# MCU.net
KiCad netlist of a schematic drawn in Altium Designer
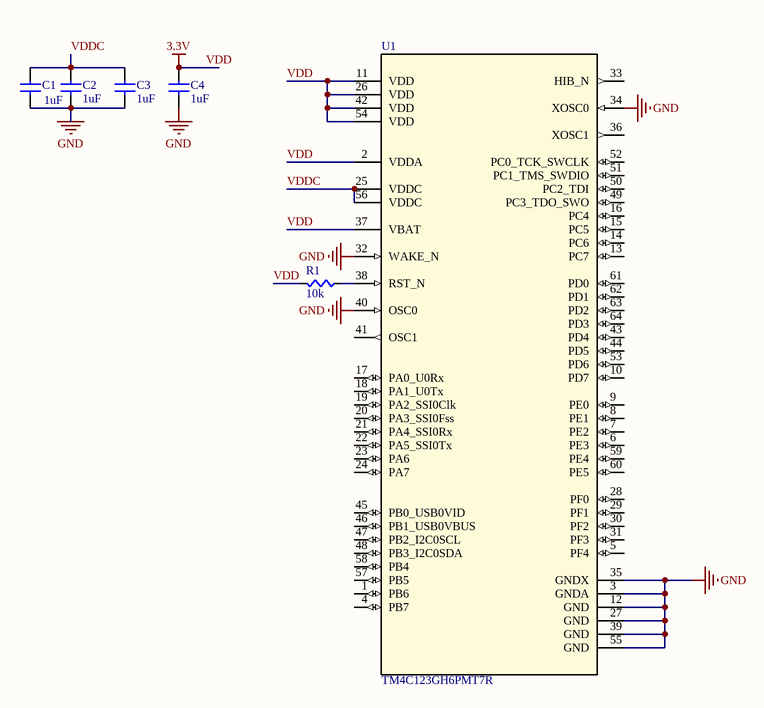
[diagram p0: MCU.SchDoc]

(export (version "E")
  (design (tool "Eeschema 10.0.6"))
  (components
    (comp (ref "C1")
      (value "1uF")
      (footprint "CAPC0805")
      (fields (field (name "Comment") "Cap"))
      (libsource (lib "Passives") (part "Cap"))
    )
    (comp (ref "C2")
      (value "1uF")
      (footprint "CAPC0805")
      (fields (field (name "Comment") "Cap"))
      (libsource (lib "Passives") (part "Cap"))
    )
    (comp (ref "C3")
      (value "1uF")
      (footprint "CAPC0805")
      (fields (field (name "Comment") "Cap"))
      (libsource (lib "Passives") (part "Cap"))
    )
    (comp (ref "C4")
      (value "1uF")
      (footprint "CAPC0805")
      (fields (field (name "Comment") "Cap"))
      (libsource (lib "Passives") (part "Cap"))
    )
    (comp (ref "R1")
      (value "10k")
      (footprint "RES0603")
      (fields (field (name "Comment") "Res"))
      (libsource (lib "Passives") (part "Res"))
    )
    (comp (ref "U1")
      (value "TM4C123GH6PMT7R")
      (footprint "TM4C123GH6PMT7R_L")
      (description "Imported")
      (fields
        (field (name "PARTNUMBER") "TM4C123GH6PMTR")
        (field (name "ALTERNATE_PARTNUMBER") "TM4C123GH6PMT")
      )
      (libsource (lib "ICs") (part "TM4C123GH6PMT7R"))
    )
  )
  (nets
    (net (code "1") (name "/VDDC") (class "Default")
      (node (ref "C1") (pin "1") (pinfunction "A_1") (pintype "passive"))
      (node (ref "C2") (pin "1") (pinfunction "A_1") (pintype "passive"))
      (node (ref "C3") (pin "1") (pinfunction "A_1") (pintype "passive"))
      (node (ref "U1") (pin "25") (pinfunction "VDDC_25") (pintype "power_in"))
      (node (ref "U1") (pin "56") (pinfunction "VDDC_56") (pintype "power_in"))
    )
    (net (code "2") (name "3.3V") (class "Default")
      (node (ref "C4") (pin "1") (pinfunction "A_1") (pintype "passive"))
      (node (ref "R1") (pin "1") (pinfunction "A_1") (pintype "passive"))
      (node (ref "U1") (pin "11") (pinfunction "VDD_11") (pintype "power_in"))
      (node (ref "U1") (pin "2") (pinfunction "VDDA_2") (pintype "power_in"))
      (node (ref "U1") (pin "26") (pinfunction "VDD_26") (pintype "power_in"))
      (node (ref "U1") (pin "37") (pinfunction "VBAT_37") (pintype "power_in"))
      (node (ref "U1") (pin "42") (pinfunction "VDD_42") (pintype "power_in"))
      (node (ref "U1") (pin "54") (pinfunction "VDD_54") (pintype "power_in"))
    )
    (net (code "3") (name "GND") (class "Default")
      (node (ref "C1") (pin "2") (pinfunction "B_2") (pintype "passive"))
      (node (ref "C2") (pin "2") (pinfunction "B_2") (pintype "passive"))
      (node (ref "C3") (pin "2") (pinfunction "B_2") (pintype "passive"))
      (node (ref "C4") (pin "2") (pinfunction "B_2") (pintype "passive"))
      (node (ref "U1") (pin "12") (pinfunction "GND_12") (pintype "power_in"))
      (node (ref "U1") (pin "27") (pinfunction "GND_27") (pintype "power_in"))
      (node (ref "U1") (pin "3") (pinfunction "GNDA_3") (pintype "power_in"))
      (node (ref "U1") (pin "32") (pinfunction "WAKE_N_32") (pintype "input"))
      (node (ref "U1") (pin "34") (pinfunction "XOSC0_34") (pintype "input"))
      (node (ref "U1") (pin "35") (pinfunction "GNDX_35") (pintype "power_in"))
      (node (ref "U1") (pin "39") (pinfunction "GND_39") (pintype "power_in"))
      (node (ref "U1") (pin "40") (pinfunction "OSC0_40") (pintype "input"))
      (node (ref "U1") (pin "55") (pinfunction "GND_55") (pintype "power_in"))
    )
    (net (code "4") (name "Net-(R1-B)") (class "Default")
      (node (ref "R1") (pin "2") (pinfunction "B_2") (pintype "passive"))
      (node (ref "U1") (pin "38") (pinfunction "RST_N_38") (pintype "input"))
    )
    (net (code "5") (name "unconnected-(U1-HIB_N-Pad33)") (class "Default")
      (node (ref "U1") (pin "33") (pinfunction "HIB_N_33") (pintype "output"))
    )
    (net (code "6") (name "unconnected-(U1-OSC1-Pad41)") (class "Default")
      (node (ref "U1") (pin "41") (pinfunction "OSC1_41") (pintype "output"))
    )
    (net (code "7") (name "unconnected-(U1-PA0_U0Rx-Pad17)") (class "Default")
      (node (ref "U1") (pin "17") (pinfunction "PA0_U0Rx_17") (pintype "bidirectional"))
    )
    (net (code "8") (name "unconnected-(U1-PA1_U0Tx-Pad18)") (class "Default")
      (node (ref "U1") (pin "18") (pinfunction "PA1_U0Tx_18") (pintype "bidirectional"))
    )
    (net (code "9") (name "unconnected-(U1-PA2_SSI0Clk-Pad19)") (class "Default")
      (node (ref "U1") (pin "19") (pinfunction "PA2_SSI0Clk_19") (pintype "bidirectional"))
    )
    (net (code "10") (name "unconnected-(U1-PA3_SSI0Fss-Pad20)") (class "Default")
      (node (ref "U1") (pin "20") (pinfunction "PA3_SSI0Fss_20") (pintype "bidirectional"))
    )
    (net (code "11") (name "unconnected-(U1-PA4_SSI0Rx-Pad21)") (class "Default")
      (node (ref "U1") (pin "21") (pinfunction "PA4_SSI0Rx_21") (pintype "bidirectional"))
    )
    (net (code "12") (name "unconnected-(U1-PA5_SSI0Tx-Pad22)") (class "Default")
      (node (ref "U1") (pin "22") (pinfunction "PA5_SSI0Tx_22") (pintype "bidirectional"))
    )
    (net (code "13") (name "unconnected-(U1-PA6-Pad23)") (class "Default")
      (node (ref "U1") (pin "23") (pinfunction "PA6_23") (pintype "bidirectional"))
    )
    (net (code "14") (name "unconnected-(U1-PA7-Pad24)") (class "Default")
      (node (ref "U1") (pin "24") (pinfunction "PA7_24") (pintype "bidirectional"))
    )
    (net (code "15") (name "unconnected-(U1-PB0_USB0VID-Pad45)") (class "Default")
      (node (ref "U1") (pin "45") (pinfunction "PB0_USB0VID_45") (pintype "bidirectional"))
    )
    (net (code "16") (name "unconnected-(U1-PB1_USB0VBUS-Pad46)") (class "Default")
      (node (ref "U1") (pin "46") (pinfunction "PB1_USB0VBUS_46") (pintype "bidirectional"))
    )
    (net (code "17") (name "unconnected-(U1-PB2_I2C0SCL-Pad47)") (class "Default")
      (node (ref "U1") (pin "47") (pinfunction "PB2_I2C0SCL_47") (pintype "bidirectional"))
    )
    (net (code "18") (name "unconnected-(U1-PB3_I2C0SDA-Pad48)") (class "Default")
      (node (ref "U1") (pin "48") (pinfunction "PB3_I2C0SDA_48") (pintype "bidirectional"))
    )
    (net (code "19") (name "unconnected-(U1-PB4-Pad58)") (class "Default")
      (node (ref "U1") (pin "58") (pinfunction "PB4_58") (pintype "bidirectional"))
    )
    (net (code "20") (name "unconnected-(U1-PB5-Pad57)") (class "Default")
      (node (ref "U1") (pin "57") (pinfunction "PB5_57") (pintype "bidirectional"))
    )
    (net (code "21") (name "unconnected-(U1-PB6-Pad1)") (class "Default")
      (node (ref "U1") (pin "1") (pinfunction "PB6_1") (pintype "bidirectional"))
    )
    (net (code "22") (name "unconnected-(U1-PB7-Pad4)") (class "Default")
      (node (ref "U1") (pin "4") (pinfunction "PB7_4") (pintype "bidirectional"))
    )
    (net (code "23") (name "unconnected-(U1-PC0_TCK_SWCLK-Pad52)") (class "Default")
      (node (ref "U1") (pin "52") (pinfunction "PC0_TCK_SWCLK_52") (pintype "bidirectional"))
    )
    (net (code "24") (name "unconnected-(U1-PC1_TMS_SWDIO-Pad51)") (class "Default")
      (node (ref "U1") (pin "51") (pinfunction "PC1_TMS_SWDIO_51") (pintype "bidirectional"))
    )
    (net (code "25") (name "unconnected-(U1-PC2_TDI-Pad50)") (class "Default")
      (node (ref "U1") (pin "50") (pinfunction "PC2_TDI_50") (pintype "bidirectional"))
    )
    (net (code "26") (name "unconnected-(U1-PC3_TDO_SWO-Pad49)") (class "Default")
      (node (ref "U1") (pin "49") (pinfunction "PC3_TDO_SWO_49") (pintype "bidirectional"))
    )
    (net (code "27") (name "unconnected-(U1-PC4-Pad16)") (class "Default")
      (node (ref "U1") (pin "16") (pinfunction "PC4_16") (pintype "bidirectional"))
    )
    (net (code "28") (name "unconnected-(U1-PC5-Pad15)") (class "Default")
      (node (ref "U1") (pin "15") (pinfunction "PC5_15") (pintype "bidirectional"))
    )
    (net (code "29") (name "unconnected-(U1-PC6-Pad14)") (class "Default")
      (node (ref "U1") (pin "14") (pinfunction "PC6_14") (pintype "bidirectional"))
    )
    (net (code "30") (name "unconnected-(U1-PC7-Pad13)") (class "Default")
      (node (ref "U1") (pin "13") (pinfunction "PC7_13") (pintype "bidirectional"))
    )
    (net (code "31") (name "unconnected-(U1-PD0-Pad61)") (class "Default")
      (node (ref "U1") (pin "61") (pinfunction "PD0_61") (pintype "bidirectional"))
    )
    (net (code "32") (name "unconnected-(U1-PD1-Pad62)") (class "Default")
      (node (ref "U1") (pin "62") (pinfunction "PD1_62") (pintype "bidirectional"))
    )
    (net (code "33") (name "unconnected-(U1-PD2-Pad63)") (class "Default")
      (node (ref "U1") (pin "63") (pinfunction "PD2_63") (pintype "bidirectional"))
    )
    (net (code "34") (name "unconnected-(U1-PD3-Pad64)") (class "Default")
      (node (ref "U1") (pin "64") (pinfunction "PD3_64") (pintype "bidirectional"))
    )
    (net (code "35") (name "unconnected-(U1-PD4-Pad43)") (class "Default")
      (node (ref "U1") (pin "43") (pinfunction "PD4_43") (pintype "bidirectional"))
    )
    (net (code "36") (name "unconnected-(U1-PD5-Pad44)") (class "Default")
      (node (ref "U1") (pin "44") (pinfunction "PD5_44") (pintype "bidirectional"))
    )
    (net (code "37") (name "unconnected-(U1-PD6-Pad53)") (class "Default")
      (node (ref "U1") (pin "53") (pinfunction "PD6_53") (pintype "bidirectional"))
    )
    (net (code "38") (name "unconnected-(U1-PD7-Pad10)") (class "Default")
      (node (ref "U1") (pin "10") (pinfunction "PD7_10") (pintype "bidirectional"))
    )
    (net (code "39") (name "unconnected-(U1-PE0-Pad9)") (class "Default")
      (node (ref "U1") (pin "9") (pinfunction "PE0_9") (pintype "bidirectional"))
    )
    (net (code "40") (name "unconnected-(U1-PE1-Pad8)") (class "Default")
      (node (ref "U1") (pin "8") (pinfunction "PE1_8") (pintype "bidirectional"))
    )
    (net (code "41") (name "unconnected-(U1-PE2-Pad7)") (class "Default")
      (node (ref "U1") (pin "7") (pinfunction "PE2_7") (pintype "bidirectional"))
    )
    (net (code "42") (name "unconnected-(U1-PE3-Pad6)") (class "Default")
      (node (ref "U1") (pin "6") (pinfunction "PE3_6") (pintype "bidirectional"))
    )
    (net (code "43") (name "unconnected-(U1-PE4-Pad59)") (class "Default")
      (node (ref "U1") (pin "59") (pinfunction "PE4_59") (pintype "bidirectional"))
    )
    (net (code "44") (name "unconnected-(U1-PE5-Pad60)") (class "Default")
      (node (ref "U1") (pin "60") (pinfunction "PE5_60") (pintype "bidirectional"))
    )
    (net (code "45") (name "unconnected-(U1-PF0-Pad28)") (class "Default")
      (node (ref "U1") (pin "28") (pinfunction "PF0_28") (pintype "bidirectional"))
    )
    (net (code "46") (name "unconnected-(U1-PF1-Pad29)") (class "Default")
      (node (ref "U1") (pin "29") (pinfunction "PF1_29") (pintype "bidirectional"))
    )
    (net (code "47") (name "unconnected-(U1-PF2-Pad30)") (class "Default")
      (node (ref "U1") (pin "30") (pinfunction "PF2_30") (pintype "bidirectional"))
    )
    (net (code "48") (name "unconnected-(U1-PF3-Pad31)") (class "Default")
      (node (ref "U1") (pin "31") (pinfunction "PF3_31") (pintype "bidirectional"))
    )
    (net (code "49") (name "unconnected-(U1-PF4-Pad5)") (class "Default")
      (node (ref "U1") (pin "5") (pinfunction "PF4_5") (pintype "bidirectional"))
    )
    (net (code "50") (name "unconnected-(U1-XOSC1-Pad36)") (class "Default")
      (node (ref "U1") (pin "36") (pinfunction "XOSC1_36") (pintype "output"))
    )
  )
)
